# SD_Card.net
KiCad netlist of a schematic drawn in Altium Designer
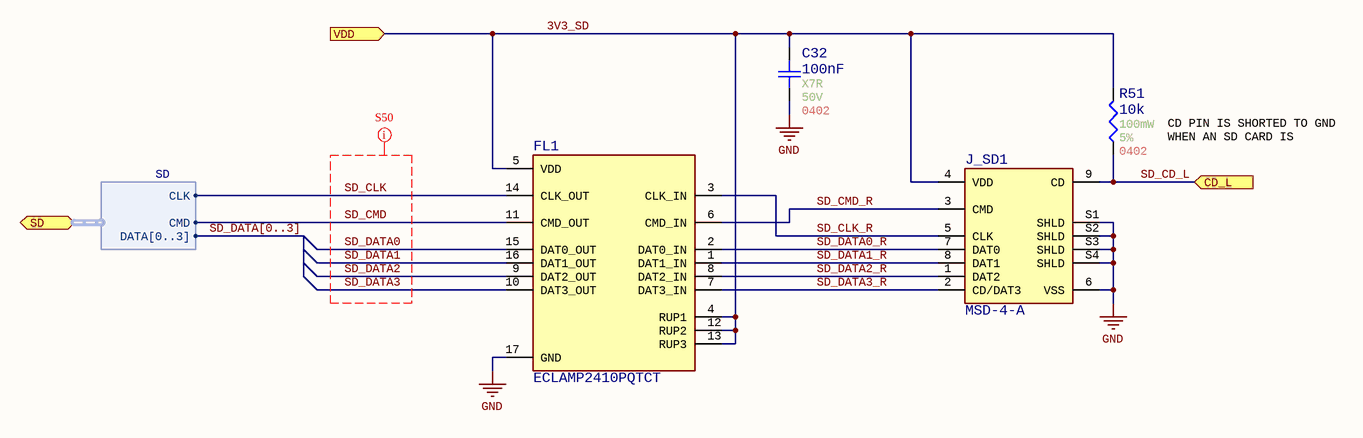
[diagram p0: SD_Card.SchDoc]

(export (version "E")
  (design (tool "Eeschema 10.0.6"))
  (components
    (comp (ref "C32")
      (value "100nF")
      (footprint "Generic 0402 capacitor")
      (fields
        (field (name "TEMPERATURE COEFFICIENT") "X7R")
        (field (name "VOLTAGE RATING") "50V")
        (field (name "CASE/PACKAGE") "0402")
        (field (name "TOLERANCE") "10%")
        (field (name "Comment") "GRT155R71H104KE01D")
      )
      (libsource (lib "Raise Robotics") (part "Unpolarized Capacitor"))
    )
    (comp (ref "FL1")
      (value "ECLAMP2410PQTCT")
      (footprint "ECLAMP2410PQTCT")
      (description "EMI Filter with Integrated ESD Protection 12pF 40dB 5V Flat Style SMD 16-Pin SLP4016P16 T/R")
      (libsource (lib "Raise Robotics") (part "ECLAMP2410PQTCT"))
    )
    (comp (ref "J_SD1")
      (value "MSD-4-A")
      (footprint "MSD-4-A")
      (fields (field (name "MANUFACTURER") "Same Sky"))
      (libsource (lib "Raise Robotics") (part "MSD-4-A"))
    )
    (comp (ref "R51")
      (value "10k")
      (footprint "Generic 0402 Resistor")
      (description "Res Thick Film 0402 10K Ohm 5% 1/10W ±200ppm/°C Molded SMD Punched Carrier T/R")
      (fields
        (field (name "POWER") "100mW")
        (field (name "TOLERANCE") "5%")
        (field (name "CASE/PACKAGE") "0402")
        (field (name "Comment") "ERJ-2GEJ103X")
      )
      (libsource (lib "Raise Robotics") (part "Resistor"))
    )
  )
  (nets
    (net (code "2") (name "/3V3_SD") (class "Default")
      (node (ref "C32") (pin "2") (pinfunction "2_2") (pintype "passive"))
      (node (ref "FL1") (pin "12") (pinfunction "RUP2_12") (pintype "passive"))
      (node (ref "FL1") (pin "13") (pinfunction "RUP3_13") (pintype "passive"))
      (node (ref "FL1") (pin "4") (pinfunction "RUP1_4") (pintype "passive"))
      (node (ref "FL1") (pin "5") (pinfunction "VDD_5") (pintype "passive"))
      (node (ref "J_SD1") (pin "4") (pinfunction "VDD_4") (pintype "passive"))
      (node (ref "R51") (pin "2") (pinfunction "2_2") (pintype "passive"))
    )
    (net (code "3") (name "/SD_CD_L") (class "Default")
      (node (ref "J_SD1") (pin "9") (pinfunction "CD_9") (pintype "passive"))
      (node (ref "R51") (pin "1") (pinfunction "1_1") (pintype "passive"))
    )
    (net (code "4") (name "/SD_CLK") (class "Default")
      (node (ref "FL1") (pin "14") (pinfunction "CLK_OUT_14") (pintype "passive"))
    )
    (net (code "5") (name "/SD_CLK_R") (class "Default")
      (node (ref "FL1") (pin "3") (pinfunction "CLK_IN_3") (pintype "passive"))
      (node (ref "J_SD1") (pin "5") (pinfunction "CLK_5") (pintype "passive"))
    )
    (net (code "6") (name "/SD_CMD") (class "Default")
      (node (ref "FL1") (pin "11") (pinfunction "CMD_OUT_11") (pintype "passive"))
    )
    (net (code "7") (name "/SD_CMD_R") (class "Default")
      (node (ref "FL1") (pin "6") (pinfunction "CMD_IN_6") (pintype "passive"))
      (node (ref "J_SD1") (pin "3") (pinfunction "CMD_3") (pintype "passive"))
    )
    (net (code "8") (name "/SD_DATA0") (class "Default")
      (node (ref "FL1") (pin "15") (pinfunction "DAT0_OUT_15") (pintype "passive"))
    )
    (net (code "9") (name "/SD_DATA0_R") (class "Default")
      (node (ref "FL1") (pin "2") (pinfunction "DAT0_IN_2") (pintype "passive"))
      (node (ref "J_SD1") (pin "7") (pinfunction "DAT0_7") (pintype "passive"))
    )
    (net (code "10") (name "/SD_DATA1") (class "Default")
      (node (ref "FL1") (pin "16") (pinfunction "DAT1_OUT_16") (pintype "passive"))
    )
    (net (code "11") (name "/SD_DATA1_R") (class "Default")
      (node (ref "FL1") (pin "1") (pinfunction "DAT1_IN_1") (pintype "passive"))
      (node (ref "J_SD1") (pin "8") (pinfunction "DAT1_8") (pintype "passive"))
    )
    (net (code "12") (name "/SD_DATA2") (class "Default")
      (node (ref "FL1") (pin "9") (pinfunction "DAT2_OUT_9") (pintype "passive"))
    )
    (net (code "13") (name "/SD_DATA2_R") (class "Default")
      (node (ref "FL1") (pin "8") (pinfunction "DAT2_IN_8") (pintype "passive"))
      (node (ref "J_SD1") (pin "1") (pinfunction "DAT2_1") (pintype "passive"))
    )
    (net (code "14") (name "/SD_DATA3") (class "Default")
      (node (ref "FL1") (pin "10") (pinfunction "DAT3_OUT_10") (pintype "passive"))
    )
    (net (code "15") (name "/SD_DATA3_R") (class "Default")
      (node (ref "FL1") (pin "7") (pinfunction "DAT3_IN_7") (pintype "passive"))
      (node (ref "J_SD1") (pin "2") (pinfunction "CD/DAT3_2") (pintype "passive"))
    )
    (net (code "18") (name "GND") (class "Default")
      (node (ref "C32") (pin "1") (pinfunction "1_1") (pintype "passive"))
      (node (ref "FL1") (pin "17") (pinfunction "GND_17") (pintype "passive"))
      (node (ref "J_SD1") (pin "6") (pinfunction "VSS_6") (pintype "passive"))
      (node (ref "J_SD1") (pin "S1") (pinfunction "SHLD_S1") (pintype "passive"))
      (node (ref "J_SD1") (pin "S2") (pinfunction "SHLD_S2") (pintype "passive"))
      (node (ref "J_SD1") (pin "S3") (pinfunction "SHLD_S3") (pintype "passive"))
      (node (ref "J_SD1") (pin "S4") (pinfunction "SHLD_S4") (pintype "passive"))
    )
  )
)
